# ESC_dev_board.net
KiCad netlist of a schematic drawn in Altium Designer
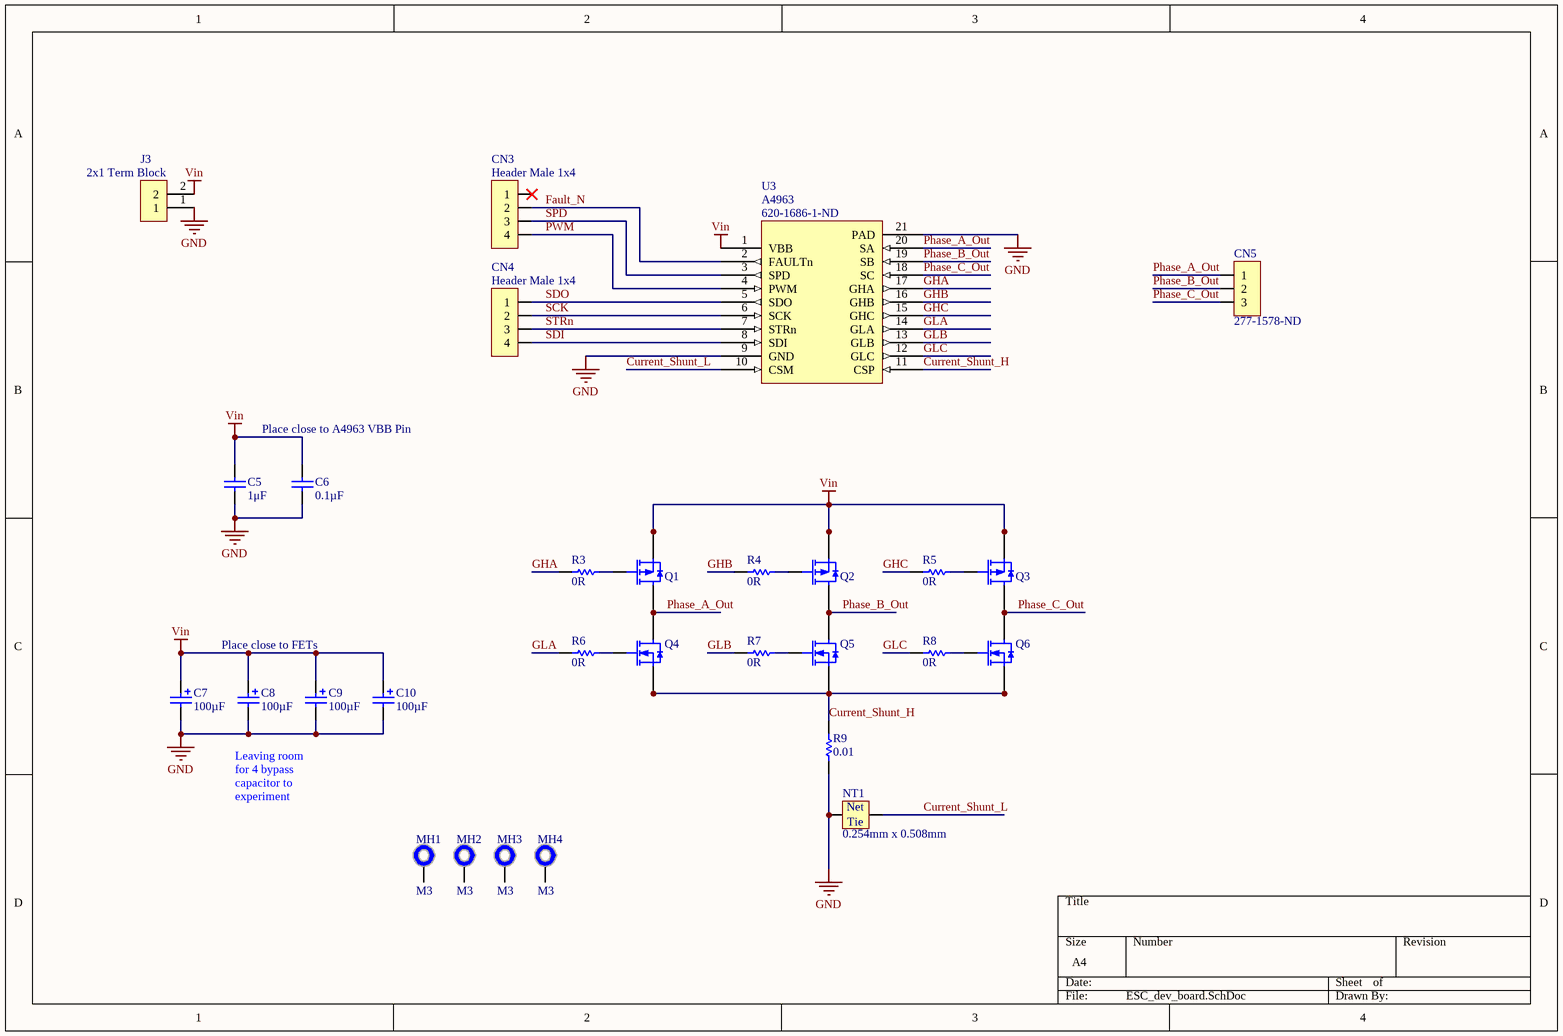
[diagram p0: ESC_dev_board.SchDoc]

(export (version "E")
  (design (tool "Eeschema 10.0.6"))
  (components
    (comp (ref "C5")
      (value "1μF")
      (footprint "CAPC1608N(0603\")")
      (description "Capacitor, Ceramic, 50V, +/- 10%, 0603 SMD, X5R")
      (fields (field (name "CREATED BY") "Lyden Smith"))
      (libsource (lib "AUVic_Integrated_Library_Capacitors") (part "1uF 50V 0603 SMD, Ceramic"))
    )
    (comp (ref "C6")
      (value "0.1uF, 50V, 10%, X7R, 0603")
      (footprint "CAPC1608N(0603\")")
      (description "0.1µF ±10% Ceramic Capacitor X7R 0603 (1608 Metric)")
      (fields (field (name "CAPACITANCE") "0.1µF") (field (name "CREATED BY") "Poorna Chander Kalidas"))
      (libsource (lib "AUVic_Integrated_Library_Capacitors") (part "0.1uF, 50V, 10%, X7R, 0603"))
    )
    (comp (ref "C7")
      (value "100µF")
      (footprint "Radial_CAN_6.6mm")
      (description "100µF 35V Aluminum Polymer Capacitor Radial, Can - SMD 30mOhm 2000 Hrs @ 105°C")
      (fields (field (name "CREATED BY") "Poorna Chander Kalidas"))
      (libsource (lib "AUVic_Integrated_Library_Capacitors") (part "100uF, 35V, 20%, 30mOhm, Alum, SMD"))
    )
    (comp (ref "C8")
      (value "100µF")
      (footprint "Radial_CAN_6.6mm")
      (description "100µF 35V Aluminum Polymer Capacitor Radial, Can - SMD 30mOhm 2000 Hrs @ 105°C")
      (fields (field (name "CREATED BY") "Poorna Chander Kalidas"))
      (libsource (lib "AUVic_Integrated_Library_Capacitors") (part "100uF, 35V, 20%, 30mOhm, Alum, SMD"))
    )
    (comp (ref "C9")
      (value "100µF")
      (footprint "Radial_CAN_6.6mm")
      (description "100µF 35V Aluminum Polymer Capacitor Radial, Can - SMD 30mOhm 2000 Hrs @ 105°C")
      (fields (field (name "CREATED BY") "Poorna Chander Kalidas"))
      (libsource (lib "AUVic_Integrated_Library_Capacitors") (part "100uF, 35V, 20%, 30mOhm, Alum, SMD"))
    )
    (comp (ref "C10")
      (value "100µF")
      (footprint "Radial_CAN_6.6mm")
      (description "100µF 35V Aluminum Polymer Capacitor Radial, Can - SMD 30mOhm 2000 Hrs @ 105°C")
      (fields (field (name "CREATED BY") "Poorna Chander Kalidas"))
      (libsource (lib "AUVic_Integrated_Library_Capacitors") (part "100uF, 35V, 20%, 30mOhm, Alum, SMD"))
    )
    (comp (ref "CN3")
      (value "Header Male 1x4")
      (footprint "Header, Male, 1X4")
      (description "1x4, Pads Pitch: 0.1\" (2.54mm), Through hole")
      (libsource (lib "AUVic_Integrated_Library_Connectors") (part "Header, Male, 1x4"))
    )
    (comp (ref "CN4")
      (value "Header Male 1x4")
      (footprint "Header, Male, 1X4")
      (description "1x4, Pads Pitch: 0.1\" (2.54mm), Through hole")
      (libsource (lib "AUVic_Integrated_Library_Connectors") (part "Header, Male, 1x4"))
    )
    (comp (ref "CN5")
      (value "3x1, Terminal Block, Pitch: 5mm, Screw, THT")
      (footprint "3x1, Terminal Block, Pitch: 5mm, Screw, THT")
      (fields
        (field (name "SUPPLIER PART NUMBER 1") "277-1578-ND")
        (field (name "PUBLISHER") "AUVic, Ashwin Sira")
        (field (name "REVIEWED BY") "*")
      )
      (libsource (lib "AUVic_Integrated_Library_Connectors") (part "3x1, Terminal Block, Pitch{colon} 5mm, Screw, THT"))
    )
    (comp (ref "J3")
      (value "2x1 Term Block")
      (footprint "2X1 Terminal Blocks Phoenix Contact 5mm")
      (fields (field (name "MADE BY") "Andy Bates"))
      (libsource (lib "AUVic_Integrated_Library_Connectors") (part "2x1 Terminal Block, 20A, 12-20AWG"))
    )
    (comp (ref "MH1")
      (value "M3")
      (footprint "Clearance_M3_PLATED")
      (description "Mounting Hole, M3, Plated")
      (fields (field (name "CREATED BY") "Ashwin Sira") (field (name "PUBLISHER") "AUVic"))
      (libsource (lib "AUVic_Integrated_Library_Virtual_Components") (part "Mounting Hole, M3, Plated"))
    )
    (comp (ref "MH2")
      (value "M3")
      (footprint "Clearance_M3_PLATED")
      (description "Mounting Hole, M3, Plated")
      (fields (field (name "CREATED BY") "Ashwin Sira") (field (name "PUBLISHER") "AUVic"))
      (libsource (lib "AUVic_Integrated_Library_Virtual_Components") (part "Mounting Hole, M3, Plated"))
    )
    (comp (ref "MH3")
      (value "M3")
      (footprint "Clearance_M3_PLATED")
      (description "Mounting Hole, M3, Plated")
      (fields (field (name "CREATED BY") "Ashwin Sira") (field (name "PUBLISHER") "AUVic"))
      (libsource (lib "AUVic_Integrated_Library_Virtual_Components") (part "Mounting Hole, M3, Plated"))
    )
    (comp (ref "MH4")
      (value "M3")
      (footprint "Clearance_M3_PLATED")
      (description "Mounting Hole, M3, Plated")
      (fields (field (name "CREATED BY") "Ashwin Sira") (field (name "PUBLISHER") "AUVic"))
      (libsource (lib "AUVic_Integrated_Library_Virtual_Components") (part "Mounting Hole, M3, Plated"))
    )
    (comp (ref "NT1")
      (value "0.254mm x 0.508mm")
      (footprint "NETTIE_20mil")
      (description "Net Tie, 20mil by 20mil")
      (fields (field (name "CREATED BY") "Ashwin Sira") (field (name "PUBLISHER") "AUVic"))
      (libsource (lib "AUVic_Integrated_Library_Virtual_Components") (part "Net Tie, 20mil"))
    )
    (comp (ref "Q1")
      (value "SI7625DN-T1-GE3")
      (footprint "PowerPAK 1212-8")
      (description "P-Channel 30V 35A (Tc) 3.7W (Ta), 52W (Tc) Surface Mount PowerPAK® 1212-8")
      (fields (field (name "CREATED BY") "Poorna Chander Kalidas"))
      (libsource (lib "AUVic_Integrated_Library_Transistors") (part "SI7625DN-T1-GE3"))
    )
    (comp (ref "Q2")
      (value "SI7625DN-T1-GE3")
      (footprint "PowerPAK 1212-8")
      (description "P-Channel 30V 35A (Tc) 3.7W (Ta), 52W (Tc) Surface Mount PowerPAK® 1212-8")
      (fields (field (name "CREATED BY") "Poorna Chander Kalidas"))
      (libsource (lib "AUVic_Integrated_Library_Transistors") (part "SI7625DN-T1-GE3"))
    )
    (comp (ref "Q3")
      (value "SI7625DN-T1-GE3")
      (footprint "PowerPAK 1212-8")
      (description "P-Channel 30V 35A (Tc) 3.7W (Ta), 52W (Tc) Surface Mount PowerPAK® 1212-8")
      (fields (field (name "CREATED BY") "Poorna Chander Kalidas"))
      (libsource (lib "AUVic_Integrated_Library_Transistors") (part "SI7625DN-T1-GE3"))
    )
    (comp (ref "Q4")
      (value "SIS476DN-T1-GE3")
      (footprint "PowerPAK 1212-8")
      (description "N-Channel 30V 40A (Tc) 3.7W (Ta), 52W (Tc) Surface Mount PowerPAK® 1212-8")
      (fields (field (name "CREATED BY") "Poorna Chander Kalidas"))
      (libsource (lib "AUVic_Integrated_Library_Transistors") (part "SIS476DN-T1-GE3"))
    )
    (comp (ref "Q5")
      (value "SIS476DN-T1-GE3")
      (footprint "PowerPAK 1212-8")
      (description "N-Channel 30V 40A (Tc) 3.7W (Ta), 52W (Tc) Surface Mount PowerPAK® 1212-8")
      (fields (field (name "CREATED BY") "Poorna Chander Kalidas"))
      (libsource (lib "AUVic_Integrated_Library_Transistors") (part "SIS476DN-T1-GE3"))
    )
    (comp (ref "Q6")
      (value "SIS476DN-T1-GE3")
      (footprint "PowerPAK 1212-8")
      (description "N-Channel 30V 40A (Tc) 3.7W (Ta), 52W (Tc) Surface Mount PowerPAK® 1212-8")
      (fields (field (name "CREATED BY") "Poorna Chander Kalidas"))
      (libsource (lib "AUVic_Integrated_Library_Transistors") (part "SIS476DN-T1-GE3"))
    )
    (comp (ref "R3")
      (value "0R")
      (footprint "RESC1608N(0603\")")
      (description "0R, 1%, 1/10W, 0603 SMD")
      (fields (field (name "MADE BY") "Ashwin Sira"))
      (libsource (lib "AUVic_Integrated_Library_Resistors") (part "0R, 1%, 1/10W, 0603 SMD"))
    )
    (comp (ref "R4")
      (value "0R")
      (footprint "RESC1608N(0603\")")
      (description "0R, 1%, 1/10W, 0603 SMD")
      (fields (field (name "MADE BY") "Ashwin Sira"))
      (libsource (lib "AUVic_Integrated_Library_Resistors") (part "0R, 1%, 1/10W, 0603 SMD"))
    )
    (comp (ref "R5")
      (value "0R")
      (footprint "RESC1608N(0603\")")
      (description "0R, 1%, 1/10W, 0603 SMD")
      (fields (field (name "MADE BY") "Ashwin Sira"))
      (libsource (lib "AUVic_Integrated_Library_Resistors") (part "0R, 1%, 1/10W, 0603 SMD"))
    )
    (comp (ref "R6")
      (value "0R")
      (footprint "RESC1608N(0603\")")
      (description "0R, 1%, 1/10W, 0603 SMD")
      (fields (field (name "MADE BY") "Ashwin Sira"))
      (libsource (lib "AUVic_Integrated_Library_Resistors") (part "0R, 1%, 1/10W, 0603 SMD"))
    )
    (comp (ref "R7")
      (value "0R")
      (footprint "RESC1608N(0603\")")
      (description "0R, 1%, 1/10W, 0603 SMD")
      (fields (field (name "MADE BY") "Ashwin Sira"))
      (libsource (lib "AUVic_Integrated_Library_Resistors") (part "0R, 1%, 1/10W, 0603 SMD"))
    )
    (comp (ref "R8")
      (value "0R")
      (footprint "RESC1608N(0603\")")
      (description "0R, 1%, 1/10W, 0603 SMD")
      (fields (field (name "MADE BY") "Ashwin Sira"))
      (libsource (lib "AUVic_Integrated_Library_Resistors") (part "0R, 1%, 1/10W, 0603 SMD"))
    )
    (comp (ref "R9")
      (value "0.01")
      (footprint "RESC6332N(2512\")")
      (description "RES 0.01 OHM 1% 3W 2512")
      (fields (field (name "CREATED BY") "Poorna Chander Kalidas"))
      (libsource (lib "AUVic_Integrated_Library_Resistors") (part "0R01, 1%, 3W, 2512 SMD"))
    )
    (comp (ref "U3")
      (value "A4963")
      (footprint "TSOP65P640X120_HS-21M")
      (description "A4963, BLDC, 3 Phase, Sensorless")
      (fields
        (field (name "SUPPLIER PART NUMBER 1") "620-1686-1-ND")
        (field (name "CREATED BY") "Poorna Chander Kalidas")
      )
      (libsource (lib "AUVic_Integrated_Library_Motor_Controllers") (part "A4963, BLDC, 3Phase"))
    )
  )
  (nets
    (net (code "1") (name "/Current_Shunt_H") (class "Default")
      (node (ref "Q4") (pin "1") (pinfunction "Source_1") (pintype "passive"))
      (node (ref "Q4") (pin "2") (pinfunction "Source_2") (pintype "passive"))
      (node (ref "Q4") (pin "3") (pinfunction "Source_3") (pintype "passive"))
      (node (ref "Q5") (pin "1") (pinfunction "Source_1") (pintype "passive"))
      (node (ref "Q5") (pin "2") (pinfunction "Source_2") (pintype "passive"))
      (node (ref "Q5") (pin "3") (pinfunction "Source_3") (pintype "passive"))
      (node (ref "Q6") (pin "1") (pinfunction "Source_1") (pintype "passive"))
      (node (ref "Q6") (pin "2") (pinfunction "Source_2") (pintype "passive"))
      (node (ref "Q6") (pin "3") (pinfunction "Source_3") (pintype "passive"))
      (node (ref "R9") (pin "2") (pinfunction "2_2") (pintype "passive"))
      (node (ref "U3") (pin "11") (pinfunction "CSP_11") (pintype "input"))
    )
    (net (code "2") (name "/Current_Shunt_L") (class "Default")
      (node (ref "NT1") (pin "2") (pinfunction "2_2") (pintype "passive"))
      (node (ref "U3") (pin "10") (pinfunction "CSM_10") (pintype "input"))
    )
    (net (code "3") (name "/Fault_N") (class "Default")
      (node (ref "CN3") (pin "2") (pinfunction "2_2") (pintype "passive"))
      (node (ref "U3") (pin "2") (pinfunction "FAULTn_2") (pintype "output"))
    )
    (net (code "4") (name "/GHA") (class "Default")
      (node (ref "R3") (pin "1") (pinfunction "1_1") (pintype "passive"))
      (node (ref "U3") (pin "17") (pinfunction "GHA_17") (pintype "output"))
    )
    (net (code "5") (name "/GHB") (class "Default")
      (node (ref "R4") (pin "1") (pinfunction "1_1") (pintype "passive"))
      (node (ref "U3") (pin "16") (pinfunction "GHB_16") (pintype "output"))
    )
    (net (code "6") (name "/GHC") (class "Default")
      (node (ref "R5") (pin "1") (pinfunction "1_1") (pintype "passive"))
      (node (ref "U3") (pin "15") (pinfunction "GHC_15") (pintype "output"))
    )
    (net (code "7") (name "/GLA") (class "Default")
      (node (ref "R6") (pin "1") (pinfunction "1_1") (pintype "passive"))
      (node (ref "U3") (pin "14") (pinfunction "GLA_14") (pintype "output"))
    )
    (net (code "8") (name "/GLB") (class "Default")
      (node (ref "R7") (pin "1") (pinfunction "1_1") (pintype "passive"))
      (node (ref "U3") (pin "13") (pinfunction "GLB_13") (pintype "output"))
    )
    (net (code "9") (name "/GLC") (class "Default")
      (node (ref "R8") (pin "1") (pinfunction "1_1") (pintype "passive"))
      (node (ref "U3") (pin "12") (pinfunction "GLC_12") (pintype "output"))
    )
    (net (code "10") (name "/PWM") (class "Default")
      (node (ref "CN3") (pin "4") (pinfunction "4_4") (pintype "passive"))
      (node (ref "U3") (pin "4") (pinfunction "PWM_4") (pintype "input"))
    )
    (net (code "11") (name "/Phase_A_Out") (class "Default")
      (node (ref "CN5") (pin "1") (pinfunction "1_1") (pintype "passive"))
      (node (ref "Q1") (pin "5") (pinfunction "Drain_5") (pintype "passive"))
      (node (ref "Q1") (pin "6") (pinfunction "Drain_6") (pintype "passive"))
      (node (ref "Q1") (pin "7") (pinfunction "Drain_7") (pintype "passive"))
      (node (ref "Q1") (pin "8") (pinfunction "Drain_8") (pintype "passive"))
      (node (ref "Q1") (pin "9") (pinfunction "Drain_9") (pintype "passive"))
      (node (ref "Q4") (pin "5") (pinfunction "Drain_5") (pintype "passive"))
      (node (ref "Q4") (pin "6") (pinfunction "Drain_6") (pintype "passive"))
      (node (ref "Q4") (pin "7") (pinfunction "Drain_7") (pintype "passive"))
      (node (ref "Q4") (pin "8") (pinfunction "Drain_8") (pintype "passive"))
      (node (ref "Q4") (pin "9") (pinfunction "Drain_9") (pintype "passive"))
      (node (ref "U3") (pin "20") (pinfunction "SA_20") (pintype "input"))
    )
    (net (code "12") (name "/Phase_B_Out") (class "Default")
      (node (ref "CN5") (pin "2") (pinfunction "2_2") (pintype "passive"))
      (node (ref "Q2") (pin "5") (pinfunction "Drain_5") (pintype "passive"))
      (node (ref "Q2") (pin "6") (pinfunction "Drain_6") (pintype "passive"))
      (node (ref "Q2") (pin "7") (pinfunction "Drain_7") (pintype "passive"))
      (node (ref "Q2") (pin "8") (pinfunction "Drain_8") (pintype "passive"))
      (node (ref "Q2") (pin "9") (pinfunction "Drain_9") (pintype "passive"))
      (node (ref "Q5") (pin "5") (pinfunction "Drain_5") (pintype "passive"))
      (node (ref "Q5") (pin "6") (pinfunction "Drain_6") (pintype "passive"))
      (node (ref "Q5") (pin "7") (pinfunction "Drain_7") (pintype "passive"))
      (node (ref "Q5") (pin "8") (pinfunction "Drain_8") (pintype "passive"))
      (node (ref "Q5") (pin "9") (pinfunction "Drain_9") (pintype "passive"))
      (node (ref "U3") (pin "19") (pinfunction "SB_19") (pintype "input"))
    )
    (net (code "13") (name "/Phase_C_Out") (class "Default")
      (node (ref "CN5") (pin "3") (pinfunction "3_3") (pintype "passive"))
      (node (ref "Q3") (pin "5") (pinfunction "Drain_5") (pintype "passive"))
      (node (ref "Q3") (pin "6") (pinfunction "Drain_6") (pintype "passive"))
      (node (ref "Q3") (pin "7") (pinfunction "Drain_7") (pintype "passive"))
      (node (ref "Q3") (pin "8") (pinfunction "Drain_8") (pintype "passive"))
      (node (ref "Q3") (pin "9") (pinfunction "Drain_9") (pintype "passive"))
      (node (ref "Q6") (pin "5") (pinfunction "Drain_5") (pintype "passive"))
      (node (ref "Q6") (pin "6") (pinfunction "Drain_6") (pintype "passive"))
      (node (ref "Q6") (pin "7") (pinfunction "Drain_7") (pintype "passive"))
      (node (ref "Q6") (pin "8") (pinfunction "Drain_8") (pintype "passive"))
      (node (ref "Q6") (pin "9") (pinfunction "Drain_9") (pintype "passive"))
      (node (ref "U3") (pin "18") (pinfunction "SC_18") (pintype "input"))
    )
    (net (code "14") (name "/SCK") (class "Default")
      (node (ref "CN4") (pin "2") (pinfunction "2_2") (pintype "passive"))
      (node (ref "U3") (pin "6") (pinfunction "SCK_6") (pintype "input"))
    )
    (net (code "15") (name "/SDI") (class "Default")
      (node (ref "CN4") (pin "4") (pinfunction "4_4") (pintype "passive"))
      (node (ref "U3") (pin "8") (pinfunction "SDI_8") (pintype "input"))
    )
    (net (code "16") (name "/SDO") (class "Default")
      (node (ref "CN4") (pin "1") (pinfunction "1_1") (pintype "passive"))
      (node (ref "U3") (pin "5") (pinfunction "SDO_5") (pintype "output"))
    )
    (net (code "17") (name "/SPD") (class "Default")
      (node (ref "CN3") (pin "3") (pinfunction "3_3") (pintype "passive"))
      (node (ref "U3") (pin "3") (pinfunction "SPD_3") (pintype "output"))
    )
    (net (code "18") (name "/STRn") (class "Default")
      (node (ref "CN4") (pin "3") (pinfunction "3_3") (pintype "passive"))
      (node (ref "U3") (pin "7") (pinfunction "STRn_7") (pintype "input"))
    )
    (net (code "19") (name "GND") (class "Default")
      (node (ref "C10") (pin "2") (pinfunction "Cathode_2") (pintype "passive"))
      (node (ref "C5") (pin "1") (pinfunction "Anode_1") (pintype "passive"))
      (node (ref "C6") (pin "1") (pinfunction "Anode_1") (pintype "passive"))
      (node (ref "C7") (pin "2") (pinfunction "Cathode_2") (pintype "passive"))
      (node (ref "C8") (pin "2") (pinfunction "Cathode_2") (pintype "passive"))
      (node (ref "C9") (pin "2") (pinfunction "Cathode_2") (pintype "passive"))
      (node (ref "J3") (pin "1") (pinfunction "1_1") (pintype "passive"))
      (node (ref "NT1") (pin "1") (pinfunction "1_1") (pintype "passive"))
      (node (ref "R9") (pin "1") (pinfunction "1_1") (pintype "passive"))
      (node (ref "U3") (pin "21") (pinfunction "PAD_21") (pintype "power_in"))
      (node (ref "U3") (pin "9") (pinfunction "GND_9") (pintype "power_in"))
    )
    (net (code "20") (name "Net-(Q1-Gate)") (class "Default")
      (node (ref "Q1") (pin "4") (pinfunction "Gate_4") (pintype "passive"))
      (node (ref "R3") (pin "2") (pinfunction "2_2") (pintype "passive"))
    )
    (net (code "21") (name "Net-(Q2-Gate)") (class "Default")
      (node (ref "Q2") (pin "4") (pinfunction "Gate_4") (pintype "passive"))
      (node (ref "R4") (pin "2") (pinfunction "2_2") (pintype "passive"))
    )
    (net (code "22") (name "Net-(Q3-Gate)") (class "Default")
      (node (ref "Q3") (pin "4") (pinfunction "Gate_4") (pintype "passive"))
      (node (ref "R5") (pin "2") (pinfunction "2_2") (pintype "passive"))
    )
    (net (code "23") (name "Net-(Q4-Gate)") (class "Default")
      (node (ref "Q4") (pin "4") (pinfunction "Gate_4") (pintype "passive"))
      (node (ref "R6") (pin "2") (pinfunction "2_2") (pintype "passive"))
    )
    (net (code "24") (name "Net-(Q5-Gate)") (class "Default")
      (node (ref "Q5") (pin "4") (pinfunction "Gate_4") (pintype "passive"))
      (node (ref "R7") (pin "2") (pinfunction "2_2") (pintype "passive"))
    )
    (net (code "25") (name "Net-(Q6-Gate)") (class "Default")
      (node (ref "Q6") (pin "4") (pinfunction "Gate_4") (pintype "passive"))
      (node (ref "R8") (pin "2") (pinfunction "2_2") (pintype "passive"))
    )
    (net (code "26") (name "Vin") (class "Default")
      (node (ref "C10") (pin "1") (pinfunction "Anode_1") (pintype "passive"))
      (node (ref "C5") (pin "2") (pinfunction "Cathode_2") (pintype "passive"))
      (node (ref "C6") (pin "2") (pinfunction "Cathode_2") (pintype "passive"))
      (node (ref "C7") (pin "1") (pinfunction "Anode_1") (pintype "passive"))
      (node (ref "C8") (pin "1") (pinfunction "Anode_1") (pintype "passive"))
      (node (ref "C9") (pin "1") (pinfunction "Anode_1") (pintype "passive"))
      (node (ref "J3") (pin "2") (pinfunction "2_2") (pintype "passive"))
      (node (ref "Q1") (pin "1") (pinfunction "Source_1") (pintype "passive"))
      (node (ref "Q1") (pin "2") (pinfunction "Source_2") (pintype "passive"))
      (node (ref "Q1") (pin "3") (pinfunction "Source_3") (pintype "passive"))
      (node (ref "Q2") (pin "1") (pinfunction "Source_1") (pintype "passive"))
      (node (ref "Q2") (pin "2") (pinfunction "Source_2") (pintype "passive"))
      (node (ref "Q2") (pin "3") (pinfunction "Source_3") (pintype "passive"))
      (node (ref "Q3") (pin "1") (pinfunction "Source_1") (pintype "passive"))
      (node (ref "Q3") (pin "2") (pinfunction "Source_2") (pintype "passive"))
      (node (ref "Q3") (pin "3") (pinfunction "Source_3") (pintype "passive"))
      (node (ref "U3") (pin "1") (pinfunction "VBB_1") (pintype "power_in"))
    )
    (net (code "27") (name "unconnected-(CN3-Pad1)") (class "Default")
      (node (ref "CN3") (pin "1") (pinfunction "1_1") (pintype "passive+no_connect"))
    )
    (net (code "28") (name "unconnected-(MH1-Pad1)") (class "Default")
      (node (ref "MH1") (pin "1") (pinfunction "1_1") (pintype "passive"))
    )
    (net (code "29") (name "unconnected-(MH2-Pad1)") (class "Default")
      (node (ref "MH2") (pin "1") (pinfunction "1_1") (pintype "passive"))
    )
    (net (code "30") (name "unconnected-(MH3-Pad1)") (class "Default")
      (node (ref "MH3") (pin "1") (pinfunction "1_1") (pintype "passive"))
    )
    (net (code "31") (name "unconnected-(MH4-Pad1)") (class "Default")
      (node (ref "MH4") (pin "1") (pinfunction "1_1") (pintype "passive"))
    )
  )
)
